# jack_breakout_mult.net
KiCad netlist of a schematic drawn in EAGLE
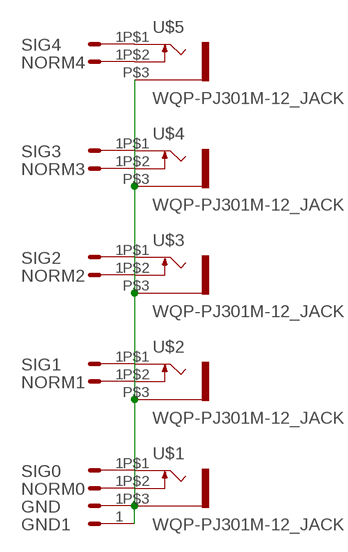
[diagram p0: schematic, sheet 1]

(export (version "E")
  (design (tool "Eeschema 10.0.6"))
  (components
    (comp (ref "GND")
      (value "HEADER/MALE/01")
      (footprint "eagle-import:HEADER_MALE_01")
      (libsource (lib "eagle-import") (part "HEADER/MALE/01"))
    )
    (comp (ref "GND1")
      (value "HEADER/MALE/01")
      (footprint "eagle-import:HEADER_MALE_01")
      (libsource (lib "eagle-import") (part "HEADER/MALE/01"))
    )
    (comp (ref "NORM0")
      (value "HEADER/MALE/01")
      (footprint "eagle-import:HEADER_MALE_01")
      (libsource (lib "eagle-import") (part "HEADER/MALE/01"))
    )
    (comp (ref "NORM1")
      (value "HEADER/MALE/01")
      (footprint "eagle-import:HEADER_MALE_01")
      (libsource (lib "eagle-import") (part "HEADER/MALE/01"))
    )
    (comp (ref "NORM2")
      (value "HEADER/MALE/01")
      (footprint "eagle-import:HEADER_MALE_01")
      (libsource (lib "eagle-import") (part "HEADER/MALE/01"))
    )
    (comp (ref "NORM3")
      (value "HEADER/MALE/01")
      (footprint "eagle-import:HEADER_MALE_01")
      (libsource (lib "eagle-import") (part "HEADER/MALE/01"))
    )
    (comp (ref "NORM4")
      (value "HEADER/MALE/01")
      (footprint "eagle-import:HEADER_MALE_01")
      (libsource (lib "eagle-import") (part "HEADER/MALE/01"))
    )
    (comp (ref "SIG0")
      (value "HEADER/MALE/01")
      (footprint "eagle-import:HEADER_MALE_01")
      (libsource (lib "eagle-import") (part "HEADER/MALE/01"))
    )
    (comp (ref "SIG1")
      (value "HEADER/MALE/01")
      (footprint "eagle-import:HEADER_MALE_01")
      (libsource (lib "eagle-import") (part "HEADER/MALE/01"))
    )
    (comp (ref "SIG2")
      (value "HEADER/MALE/01")
      (footprint "eagle-import:HEADER_MALE_01")
      (libsource (lib "eagle-import") (part "HEADER/MALE/01"))
    )
    (comp (ref "SIG3")
      (value "HEADER/MALE/01")
      (footprint "eagle-import:HEADER_MALE_01")
      (libsource (lib "eagle-import") (part "HEADER/MALE/01"))
    )
    (comp (ref "SIG4")
      (value "HEADER/MALE/01")
      (footprint "eagle-import:HEADER_MALE_01")
      (libsource (lib "eagle-import") (part "HEADER/MALE/01"))
    )
    (comp (ref "U$1")
      (value "WQP-PJ301M-12_JACK")
      (footprint "eagle-import:WQP-PJ301M-12_JACK")
      (libsource (lib "eagle-import") (part "WQP-PJ301M-12_JACK"))
    )
    (comp (ref "U$2")
      (value "WQP-PJ301M-12_JACK")
      (footprint "eagle-import:WQP-PJ301M-12_JACK")
      (libsource (lib "eagle-import") (part "WQP-PJ301M-12_JACK"))
    )
    (comp (ref "U$3")
      (value "WQP-PJ301M-12_JACK")
      (footprint "eagle-import:WQP-PJ301M-12_JACK")
      (libsource (lib "eagle-import") (part "WQP-PJ301M-12_JACK"))
    )
    (comp (ref "U$4")
      (value "WQP-PJ301M-12_JACK")
      (footprint "eagle-import:WQP-PJ301M-12_JACK")
      (libsource (lib "eagle-import") (part "WQP-PJ301M-12_JACK"))
    )
    (comp (ref "U$5")
      (value "WQP-PJ301M-12_JACK")
      (footprint "eagle-import:WQP-PJ301M-12_JACK")
      (libsource (lib "eagle-import") (part "WQP-PJ301M-12_JACK"))
    )
  )
  (nets
    (net (code "1") (name "Net-(GND-3)") (class "Default")
      (node (ref "GND") (pin "1") (pinfunction "3_1") (pintype "passive"))
      (node (ref "GND1") (pin "1") (pinfunction "3_1") (pintype "passive"))
      (node (ref "U$1") (pin "P$3") (pinfunction "1_P$3") (pintype "passive"))
      (node (ref "U$2") (pin "P$3") (pinfunction "1_P$3") (pintype "passive"))
      (node (ref "U$3") (pin "P$3") (pinfunction "1_P$3") (pintype "passive"))
      (node (ref "U$4") (pin "P$3") (pinfunction "1_P$3") (pintype "passive"))
      (node (ref "U$5") (pin "P$3") (pinfunction "1_P$3") (pintype "passive"))
    )
    (net (code "2") (name "Net-(NORM0-3)") (class "Default")
      (node (ref "NORM0") (pin "1") (pinfunction "3_1") (pintype "passive"))
      (node (ref "U$1") (pin "P$2") (pinfunction "3_P$2") (pintype "passive"))
    )
    (net (code "3") (name "Net-(NORM1-3)") (class "Default")
      (node (ref "NORM1") (pin "1") (pinfunction "3_1") (pintype "passive"))
      (node (ref "U$2") (pin "P$2") (pinfunction "3_P$2") (pintype "passive"))
    )
    (net (code "4") (name "Net-(NORM2-3)") (class "Default")
      (node (ref "NORM2") (pin "1") (pinfunction "3_1") (pintype "passive"))
      (node (ref "U$3") (pin "P$2") (pinfunction "3_P$2") (pintype "passive"))
    )
    (net (code "5") (name "Net-(NORM3-3)") (class "Default")
      (node (ref "NORM3") (pin "1") (pinfunction "3_1") (pintype "passive"))
      (node (ref "U$4") (pin "P$2") (pinfunction "3_P$2") (pintype "passive"))
    )
    (net (code "6") (name "Net-(NORM4-3)") (class "Default")
      (node (ref "NORM4") (pin "1") (pinfunction "3_1") (pintype "passive"))
      (node (ref "U$5") (pin "P$2") (pinfunction "3_P$2") (pintype "passive"))
    )
    (net (code "7") (name "Net-(SIG0-3)") (class "Default")
      (node (ref "SIG0") (pin "1") (pinfunction "3_1") (pintype "passive"))
      (node (ref "U$1") (pin "P$1") (pinfunction "2_P$1") (pintype "passive"))
    )
    (net (code "8") (name "Net-(SIG1-3)") (class "Default")
      (node (ref "SIG1") (pin "1") (pinfunction "3_1") (pintype "passive"))
      (node (ref "U$2") (pin "P$1") (pinfunction "2_P$1") (pintype "passive"))
    )
    (net (code "9") (name "Net-(SIG2-3)") (class "Default")
      (node (ref "SIG2") (pin "1") (pinfunction "3_1") (pintype "passive"))
      (node (ref "U$3") (pin "P$1") (pinfunction "2_P$1") (pintype "passive"))
    )
    (net (code "10") (name "Net-(SIG3-3)") (class "Default")
      (node (ref "SIG3") (pin "1") (pinfunction "3_1") (pintype "passive"))
      (node (ref "U$4") (pin "P$1") (pinfunction "2_P$1") (pintype "passive"))
    )
    (net (code "11") (name "Net-(SIG4-3)") (class "Default")
      (node (ref "SIG4") (pin "1") (pinfunction "3_1") (pintype "passive"))
      (node (ref "U$5") (pin "P$1") (pinfunction "2_P$1") (pintype "passive"))
    )
  )
)
